# MCU.net
KiCad netlist of a schematic drawn in Altium Designer
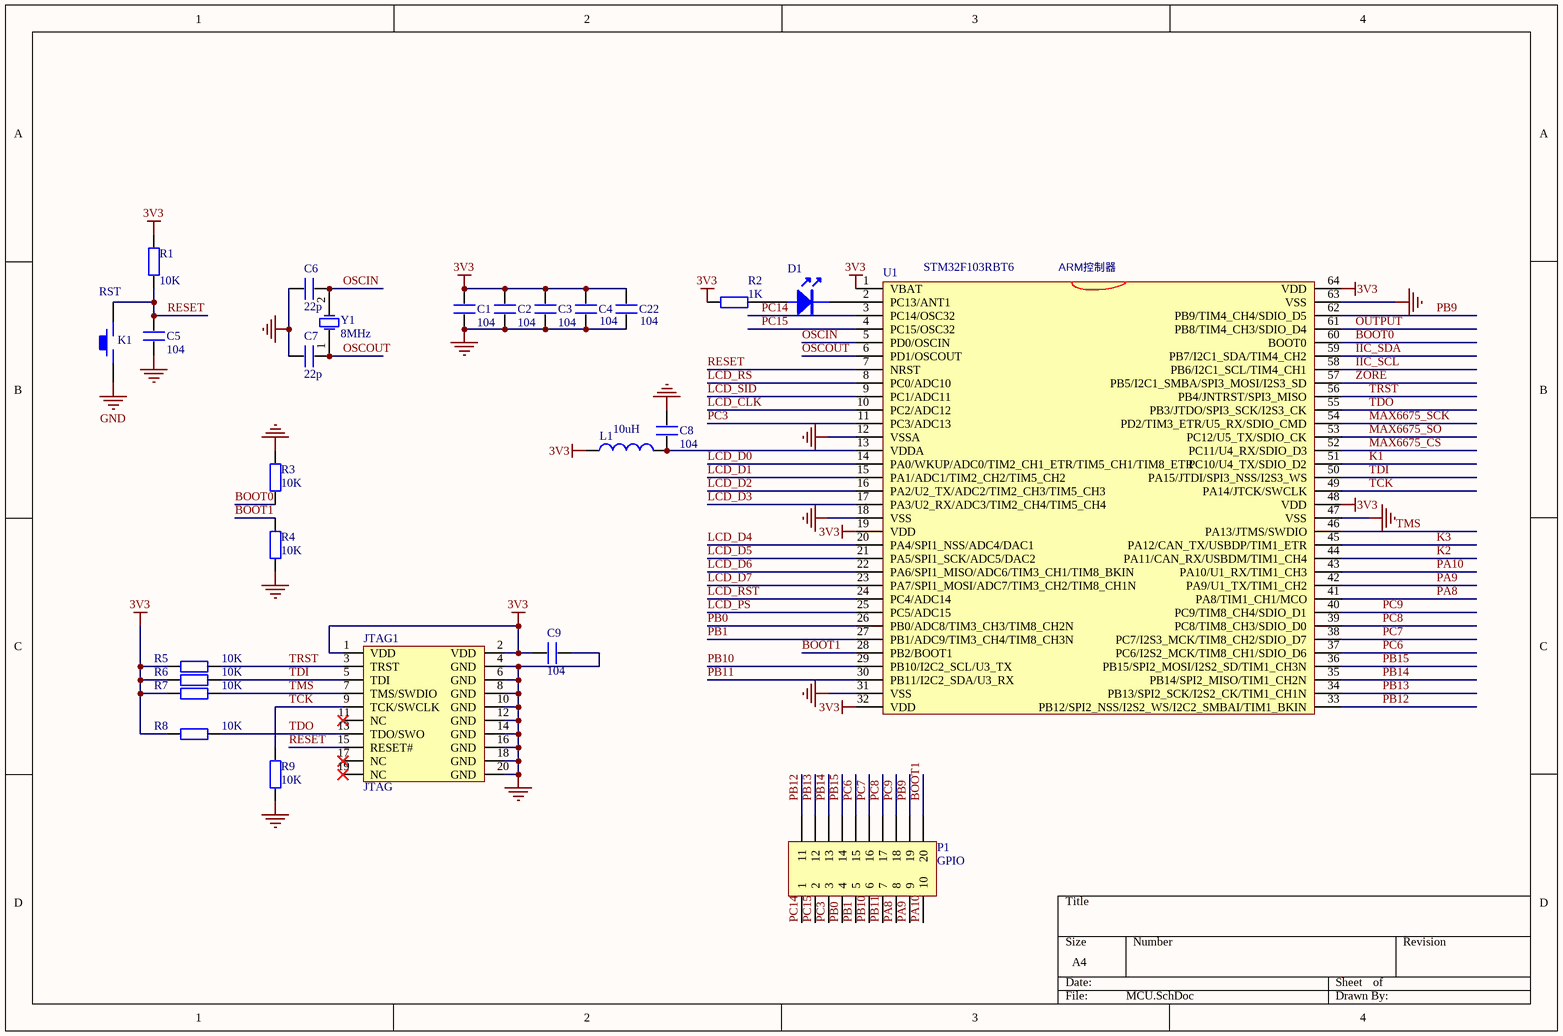
[diagram p0: MCU.SchDoc]

(export (version "E")
  (design (tool "Eeschema 10.0.6"))
  (components
    (comp (ref "C1") (value "104") (footprint "1206") (libsource (lib "MiniSTM32 V3.0封装库") (part "C")))
    (comp (ref "C2") (value "104") (footprint "1206") (libsource (lib "MiniSTM32 V3.0封装库") (part "C")))
    (comp (ref "C3") (value "104") (footprint "1206") (libsource (lib "MiniSTM32 V3.0封装库") (part "C")))
    (comp (ref "C4") (value "104") (footprint "1206") (libsource (lib "MiniSTM32 V3.0封装库") (part "C")))
    (comp (ref "C5") (value "104") (footprint "1206") (libsource (lib "MiniSTM32 V3.0封装库") (part "C")))
    (comp (ref "C6") (value "22p") (footprint "1206") (libsource (lib "MiniSTM32 V3.0封装库") (part "C")))
    (comp (ref "C7") (value "22p") (footprint "1206") (libsource (lib "MiniSTM32 V3.0封装库") (part "C")))
    (comp (ref "C8") (value "104") (footprint "1206") (libsource (lib "MiniSTM32 V3.0封装库") (part "C")))
    (comp (ref "C9") (value "104") (footprint "1206") (libsource (lib "MiniSTM32 V3.0封装库") (part "C")))
    (comp (ref "C22") (value "104") (footprint "1206") (libsource (lib "MiniSTM32 V3.0封装库") (part "C")))
    (comp (ref "D1") (value "~") (footprint "李建国1:LED") (libsource (lib "二极管") (part "发光二极管")))
    (comp (ref "JTAG1")
      (value "JTAG")
      (footprint "JTAG_20")
      (libsource (lib "MiniSTM32 V3.0封装库") (part "JTAG"))
    )
    (comp (ref "K1") (value "RST") (footprint "KEY_M") (libsource (lib "底板封装库") (part "KEY_M")))
    (comp (ref "L1")
      (value "10uH")
      (footprint "1206")
      (description "Inductor")
      (fields (field (name "PUBLISHER") "Altium Limited"))
      (libsource (lib "Miscellaneous Devices") (part "Inductor"))
    )
    (comp (ref "P1")
      (value "GPIO")
      (footprint "HDR2X10_CEN")
      (description "Header, 10-Pin, Dual row")
      (fields (field (name "PUBLISHER") "Altium Limited"))
      (libsource (lib "Miscellaneous Connectors") (part "Header 10X2A"))
    )
    (comp (ref "R1")
      (value "10K")
      (footprint "1206")
      (description "Resistor")
      (fields (field (name "PUBLISHER") "Altium Limited"))
      (libsource (lib "") (part "Res2_3"))
    )
    (comp (ref "R2")
      (value "1K")
      (footprint "1206")
      (description "Resistor")
      (fields (field (name "PUBLISHER") "Altium Limited"))
      (libsource (lib "") (part "Res2_1"))
    )
    (comp (ref "R3")
      (value "10K")
      (footprint "1206")
      (description "Resistor")
      (fields (field (name "PUBLISHER") "Altium Limited"))
      (libsource (lib "") (part "Res2_2"))
    )
    (comp (ref "R4")
      (value "10K")
      (footprint "1206")
      (description "Resistor")
      (fields (field (name "PUBLISHER") "Altium Limited"))
      (libsource (lib "") (part "Res2_2"))
    )
    (comp (ref "R5")
      (value "10K")
      (footprint "1206")
      (description "Resistor")
      (fields (field (name "PUBLISHER") "Altium Limited"))
      (libsource (lib "") (part "Res2_1"))
    )
    (comp (ref "R6")
      (value "10K")
      (footprint "1206")
      (description "Resistor")
      (fields (field (name "PUBLISHER") "Altium Limited"))
      (libsource (lib "Miscellaneous Devices") (part "Res2"))
    )
    (comp (ref "R7")
      (value "10K")
      (footprint "1206")
      (description "Resistor")
      (fields (field (name "PUBLISHER") "Altium Limited"))
      (libsource (lib "Miscellaneous Devices") (part "Res2"))
    )
    (comp (ref "R8")
      (value "10K")
      (footprint "1206")
      (description "Resistor")
      (fields (field (name "PUBLISHER") "Altium Limited"))
      (libsource (lib "Miscellaneous Devices") (part "Res2"))
    )
    (comp (ref "R9")
      (value "10K")
      (footprint "1206")
      (description "Resistor")
      (fields (field (name "PUBLISHER") "Altium Limited"))
      (libsource (lib "") (part "Res2_2"))
    )
    (comp (ref "U1")
      (value "STM32F103RBT6")
      (footprint "LQFP64")
      (libsource (lib "MiniSTM32 V3.0封装库") (part "STM32F103RDT6"))
    )
    (comp (ref "Y1")
      (value "8MHz")
      (footprint "XTAL_US")
      (description "Crystal Oscillator")
      (fields (field (name "PUBLISHER") "Altium Limited"))
      (libsource (lib "MiniSTM32 V3.0封装库") (part "XTAL"))
    )
  )
  (nets
    (net (code "1") (name "/BOOT0") (class "Default")
      (node (ref "R3") (pin "1") (pinfunction "1_1") (pintype "passive"))
      (node (ref "U1") (pin "60") (pinfunction "BOOT0_60") (pintype "passive"))
    )
    (net (code "2") (name "/BOOT1") (class "Default")
      (node (ref "P1") (pin "20") (pinfunction "20_20") (pintype "passive"))
      (node (ref "R4") (pin "2") (pinfunction "2_2") (pintype "passive"))
      (node (ref "U1") (pin "28") (pinfunction "PB2/BOOT1_28") (pintype "passive"))
    )
    (net (code "3") (name "/IIC_SCL") (class "Default")
      (node (ref "U1") (pin "58") (pinfunction "PB6/I2C1_SCL/TIM4_CH1_58") (pintype "passive"))
    )
    (net (code "4") (name "/IIC_SDA") (class "Default")
      (node (ref "U1") (pin "59") (pinfunction "PB7/I2C1_SDA/TIM4_CH2_59") (pintype "passive"))
    )
    (net (code "5") (name "/K1") (class "Default")
      (node (ref "U1") (pin "51") (pinfunction "PC10/U4_TX/SDIO_D2_51") (pintype "passive"))
    )
    (net (code "6") (name "/K2") (class "Default")
      (node (ref "U1") (pin "44") (pinfunction "PA11/CAN_RX/USBDM/TIM1_CH4_44") (pintype "passive"))
    )
    (net (code "7") (name "/K3") (class "Default")
      (node (ref "U1") (pin "45") (pinfunction "PA12/CAN_TX/USBDP/TIM1_ETR_45") (pintype "passive"))
    )
    (net (code "8") (name "/LCD_CLK") (class "Default")
      (node (ref "U1") (pin "10") (pinfunction "PC2/ADC12_10") (pintype "passive"))
    )
    (net (code "9") (name "/LCD_D0") (class "Default")
      (node (ref "U1") (pin "14") (pinfunction "PA0/WKUP/ADC0/TIM2_CH1_ETR/TIM5_CH1/TIM8_ETR_14") (pintype "passive"))
    )
    (net (code "10") (name "/LCD_D1") (class "Default")
      (node (ref "U1") (pin "15") (pinfunction "PA1/ADC1/TIM2_CH2/TIM5_CH2_15") (pintype "passive"))
    )
    (net (code "11") (name "/LCD_D2") (class "Default")
      (node (ref "U1") (pin "16") (pinfunction "PA2/U2_TX/ADC2/TIM2_CH3/TIM5_CH3_16") (pintype "passive"))
    )
    (net (code "12") (name "/LCD_D3") (class "Default")
      (node (ref "U1") (pin "17") (pinfunction "PA3/U2_RX/ADC3/TIM2_CH4/TIM5_CH4_17") (pintype "passive"))
    )
    (net (code "13") (name "/LCD_D4") (class "Default")
      (node (ref "U1") (pin "20") (pinfunction "PA4/SPI1_NSS/ADC4/DAC1_20") (pintype "passive"))
    )
    (net (code "14") (name "/LCD_D5") (class "Default")
      (node (ref "U1") (pin "21") (pinfunction "PA5/SPI1_SCK/ADC5/DAC2_21") (pintype "passive"))
    )
    (net (code "15") (name "/LCD_D6") (class "Default")
      (node (ref "U1") (pin "22") (pinfunction "PA6/SPI1_MISO/ADC6/TIM3_CH1/TIM8_BKIN_22") (pintype "passive"))
    )
    (net (code "16") (name "/LCD_D7") (class "Default")
      (node (ref "U1") (pin "23") (pinfunction "PA7/SPI1_MOSI/ADC7/TIM3_CH2/TIM8_CH1N_23") (pintype "passive"))
    )
    (net (code "17") (name "/LCD_PS") (class "Default")
      (node (ref "U1") (pin "25") (pinfunction "PC5/ADC15_25") (pintype "passive"))
    )
    (net (code "18") (name "/LCD_RS") (class "Default")
      (node (ref "U1") (pin "8") (pinfunction "PC0/ADC10_8") (pintype "passive"))
    )
    (net (code "19") (name "/LCD_RST") (class "Default")
      (node (ref "U1") (pin "24") (pinfunction "PC4/ADC14_24") (pintype "passive"))
    )
    (net (code "20") (name "/LCD_SID") (class "Default")
      (node (ref "U1") (pin "9") (pinfunction "PC1/ADC11_9") (pintype "passive"))
    )
    (net (code "21") (name "/MAX6675_CS") (class "Default")
      (node (ref "U1") (pin "52") (pinfunction "PC11/U4_RX/SDIO_D3_52") (pintype "passive"))
    )
    (net (code "22") (name "/MAX6675_SCK") (class "Default")
      (node (ref "U1") (pin "54") (pinfunction "PD2/TIM3_ETR/U5_RX/SDIO_CMD_54") (pintype "passive"))
    )
    (net (code "23") (name "/MAX6675_SO") (class "Default")
      (node (ref "U1") (pin "53") (pinfunction "PC12/U5_TX/SDIO_CK_53") (pintype "passive"))
    )
    (net (code "24") (name "/OSCIN") (class "Default")
      (node (ref "C6") (pin "1") (pintype "passive"))
      (node (ref "U1") (pin "5") (pinfunction "PD0/OSCIN_5") (pintype "passive"))
      (node (ref "Y1") (pin "2") (pinfunction "OSC2_2") (pintype "passive"))
    )
    (net (code "25") (name "/OSCOUT") (class "Default")
      (node (ref "C7") (pin "2") (pintype "passive"))
      (node (ref "U1") (pin "6") (pinfunction "PD1/OSCOUT_6") (pintype "passive"))
      (node (ref "Y1") (pin "1") (pinfunction "OSC1_1") (pintype "passive"))
    )
    (net (code "26") (name "/OUTPUT") (class "Default")
      (node (ref "U1") (pin "61") (pinfunction "PB8/TIM4_CH3/SDIO_D4_61") (pintype "passive"))
    )
    (net (code "27") (name "/PA8") (class "Default")
      (node (ref "P1") (pin "8") (pinfunction "8_8") (pintype "passive"))
      (node (ref "U1") (pin "41") (pinfunction "PA8/TIM1_CH1/MCO_41") (pintype "passive"))
    )
    (net (code "28") (name "/PA9") (class "Default")
      (node (ref "P1") (pin "9") (pinfunction "9_9") (pintype "passive"))
      (node (ref "U1") (pin "42") (pinfunction "PA9/U1_TX/TIM1_CH2_42") (pintype "passive"))
    )
    (net (code "29") (name "/PA10") (class "Default")
      (node (ref "P1") (pin "10") (pinfunction "10_10") (pintype "passive"))
      (node (ref "U1") (pin "43") (pinfunction "PA10/U1_RX/TIM1_CH3_43") (pintype "passive"))
    )
    (net (code "30") (name "/PB0") (class "Default")
      (node (ref "P1") (pin "4") (pinfunction "4_4") (pintype "passive"))
      (node (ref "U1") (pin "26") (pinfunction "PB0/ADC8/TIM3_CH3/TIM8_CH2N_26") (pintype "passive"))
    )
    (net (code "31") (name "/PB1") (class "Default")
      (node (ref "P1") (pin "5") (pinfunction "5_5") (pintype "passive"))
      (node (ref "U1") (pin "27") (pinfunction "PB1/ADC9/TIM3_CH4/TIM8_CH3N_27") (pintype "passive"))
    )
    (net (code "32") (name "/PB9") (class "Default")
      (node (ref "P1") (pin "19") (pinfunction "19_19") (pintype "passive"))
      (node (ref "U1") (pin "62") (pinfunction "PB9/TIM4_CH4/SDIO_D5_62") (pintype "passive"))
    )
    (net (code "33") (name "/PB10") (class "Default")
      (node (ref "P1") (pin "6") (pinfunction "6_6") (pintype "passive"))
      (node (ref "U1") (pin "29") (pinfunction "PB10/I2C2_SCL/U3_TX_29") (pintype "passive"))
    )
    (net (code "34") (name "/PB11") (class "Default")
      (node (ref "P1") (pin "7") (pinfunction "7_7") (pintype "passive"))
      (node (ref "U1") (pin "30") (pinfunction "PB11/I2C2_SDA/U3_RX_30") (pintype "passive"))
    )
    (net (code "35") (name "/PB12") (class "Default")
      (node (ref "P1") (pin "11") (pinfunction "11_11") (pintype "passive"))
      (node (ref "U1") (pin "33") (pinfunction "PB12/SPI2_NSS/I2S2_WS/I2C2_SMBAI/TIM1_BKIN_33") (pintype "passive"))
    )
    (net (code "36") (name "/PB13") (class "Default")
      (node (ref "P1") (pin "12") (pinfunction "12_12") (pintype "passive"))
      (node (ref "U1") (pin "34") (pinfunction "PB13/SPI2_SCK/I2S2_CK/TIM1_CH1N_34") (pintype "passive"))
    )
    (net (code "37") (name "/PB14") (class "Default")
      (node (ref "P1") (pin "13") (pinfunction "13_13") (pintype "passive"))
      (node (ref "U1") (pin "35") (pinfunction "PB14/SPI2_MISO/TIM1_CH2N_35") (pintype "passive"))
    )
    (net (code "38") (name "/PB15") (class "Default")
      (node (ref "P1") (pin "14") (pinfunction "14_14") (pintype "passive"))
      (node (ref "U1") (pin "36") (pinfunction "PB15/SPI2_MOSI/I2S2_SD/TIM1_CH3N_36") (pintype "passive"))
    )
    (net (code "39") (name "/PC3") (class "Default")
      (node (ref "P1") (pin "3") (pinfunction "3_3") (pintype "passive"))
      (node (ref "U1") (pin "11") (pinfunction "PC3/ADC13_11") (pintype "passive"))
    )
    (net (code "40") (name "/PC6") (class "Default")
      (node (ref "P1") (pin "15") (pinfunction "15_15") (pintype "passive"))
      (node (ref "U1") (pin "37") (pinfunction "PC6/I2S2_MCK/TIM8_CH1/SDIO_D6_37") (pintype "passive"))
    )
    (net (code "41") (name "/PC7") (class "Default")
      (node (ref "P1") (pin "16") (pinfunction "16_16") (pintype "passive"))
      (node (ref "U1") (pin "38") (pinfunction "PC7/I2S3_MCK/TIM8_CH2/SDIO_D7_38") (pintype "passive"))
    )
    (net (code "42") (name "/PC8") (class "Default")
      (node (ref "P1") (pin "17") (pinfunction "17_17") (pintype "passive"))
      (node (ref "U1") (pin "39") (pinfunction "PC8/TIM8_CH3/SDIO_D0_39") (pintype "passive"))
    )
    (net (code "43") (name "/PC9") (class "Default")
      (node (ref "P1") (pin "18") (pinfunction "18_18") (pintype "passive"))
      (node (ref "U1") (pin "40") (pinfunction "PC9/TIM8_CH4/SDIO_D1_40") (pintype "passive"))
    )
    (net (code "44") (name "/PC14") (class "Default")
      (node (ref "P1") (pin "1") (pinfunction "1_1") (pintype "passive"))
      (node (ref "U1") (pin "3") (pinfunction "PC14/OSC32_3") (pintype "passive"))
    )
    (net (code "45") (name "/PC15") (class "Default")
      (node (ref "P1") (pin "2") (pinfunction "2_2") (pintype "passive"))
      (node (ref "U1") (pin "4") (pinfunction "PC15/OSC32_4") (pintype "passive"))
    )
    (net (code "46") (name "/RESET") (class "Default")
      (node (ref "C5") (pin "1") (pintype "passive"))
      (node (ref "JTAG1") (pin "15") (pinfunction "RESET#_15") (pintype "passive"))
      (node (ref "K1") (pin "2") (pinfunction "2_2") (pintype "passive"))
      (node (ref "R1") (pin "2") (pinfunction "2_2") (pintype "passive"))
      (node (ref "U1") (pin "7") (pinfunction "NRST_7") (pintype "passive"))
    )
    (net (code "47") (name "/TCK") (class "Default")
      (node (ref "JTAG1") (pin "9") (pinfunction "TCK/SWCLK_9") (pintype "passive"))
      (node (ref "R9") (pin "2") (pinfunction "2_2") (pintype "passive"))
      (node (ref "U1") (pin "49") (pinfunction "PA14/JTCK/SWCLK_49") (pintype "passive"))
    )
    (net (code "48") (name "/TDI") (class "Default")
      (node (ref "JTAG1") (pin "5") (pinfunction "TDI_5") (pintype "passive"))
      (node (ref "R6") (pin "1") (pinfunction "1_1") (pintype "passive"))
      (node (ref "U1") (pin "50") (pinfunction "PA15/JTDI/SPI3_NSS/I2S3_WS_50") (pintype "passive"))
    )
    (net (code "49") (name "/TDO") (class "Default")
      (node (ref "JTAG1") (pin "13") (pinfunction "TDO/SWO_13") (pintype "passive"))
      (node (ref "R8") (pin "1") (pinfunction "1_1") (pintype "passive"))
      (node (ref "U1") (pin "55") (pinfunction "PB3/JTDO/SPI3_SCK/I2S3_CK_55") (pintype "passive"))
    )
    (net (code "50") (name "/TMS") (class "Default")
      (node (ref "JTAG1") (pin "7") (pinfunction "TMS/SWDIO_7") (pintype "passive"))
      (node (ref "R7") (pin "1") (pinfunction "1_1") (pintype "passive"))
      (node (ref "U1") (pin "46") (pinfunction "PA13/JTMS/SWDIO_46") (pintype "passive"))
    )
    (net (code "51") (name "/TRST") (class "Default")
      (node (ref "JTAG1") (pin "3") (pinfunction "TRST_3") (pintype "passive"))
      (node (ref "R5") (pin "2") (pinfunction "2_2") (pintype "passive"))
      (node (ref "U1") (pin "56") (pinfunction "PB4/JNTRST/SPI3_MISO_56") (pintype "passive"))
    )
    (net (code "52") (name "/ZORE") (class "Default")
      (node (ref "U1") (pin "57") (pinfunction "PB5/I2C1_SMBA/SPI3_MOSI/I2S3_SD_57") (pintype "passive"))
    )
    (net (code "53") (name "3V3") (class "Default")
      (node (ref "C1") (pin "1") (pintype "passive"))
      (node (ref "C2") (pin "1") (pintype "passive"))
      (node (ref "C22") (pin "1") (pintype "passive"))
      (node (ref "C3") (pin "1") (pintype "passive"))
      (node (ref "C4") (pin "1") (pintype "passive"))
      (node (ref "C9") (pin "1") (pintype "passive"))
      (node (ref "JTAG1") (pin "1") (pinfunction "VDD_1") (pintype "passive"))
      (node (ref "JTAG1") (pin "2") (pinfunction "VDD_2") (pintype "passive"))
      (node (ref "L1") (pin "1") (pinfunction "1_1") (pintype "passive"))
      (node (ref "R1") (pin "1") (pinfunction "1_1") (pintype "passive"))
      (node (ref "R2") (pin "1") (pinfunction "1_1") (pintype "passive"))
      (node (ref "R5") (pin "1") (pinfunction "1_1") (pintype "passive"))
      (node (ref "R6") (pin "2") (pinfunction "2_2") (pintype "passive"))
      (node (ref "R7") (pin "2") (pinfunction "2_2") (pintype "passive"))
      (node (ref "R8") (pin "2") (pinfunction "2_2") (pintype "passive"))
      (node (ref "U1") (pin "1") (pinfunction "VBAT_1") (pintype "passive"))
      (node (ref "U1") (pin "19") (pinfunction "VDD_19") (pintype "passive"))
      (node (ref "U1") (pin "32") (pinfunction "VDD_32") (pintype "passive"))
      (node (ref "U1") (pin "48") (pinfunction "VDD_48") (pintype "passive"))
      (node (ref "U1") (pin "64") (pinfunction "VDD_64") (pintype "passive"))
    )
    (net (code "54") (name "GND") (class "Default")
      (node (ref "C1") (pin "2") (pintype "passive"))
      (node (ref "C2") (pin "2") (pintype "passive"))
      (node (ref "C22") (pin "2") (pintype "passive"))
      (node (ref "C3") (pin "2") (pintype "passive"))
      (node (ref "C4") (pin "2") (pintype "passive"))
      (node (ref "C5") (pin "2") (pintype "passive"))
      (node (ref "C6") (pin "2") (pintype "passive"))
      (node (ref "C7") (pin "1") (pintype "passive"))
      (node (ref "C8") (pin "1") (pintype "passive"))
      (node (ref "C9") (pin "2") (pintype "passive"))
      (node (ref "JTAG1") (pin "10") (pinfunction "GND_10") (pintype "passive"))
      (node (ref "JTAG1") (pin "12") (pinfunction "GND_12") (pintype "passive"))
      (node (ref "JTAG1") (pin "14") (pinfunction "GND_14") (pintype "passive"))
      (node (ref "JTAG1") (pin "16") (pinfunction "GND_16") (pintype "passive"))
      (node (ref "JTAG1") (pin "18") (pinfunction "GND_18") (pintype "passive"))
      (node (ref "JTAG1") (pin "20") (pinfunction "GND_20") (pintype "passive"))
      (node (ref "JTAG1") (pin "4") (pinfunction "GND_4") (pintype "passive"))
      (node (ref "JTAG1") (pin "6") (pinfunction "GND_6") (pintype "passive"))
      (node (ref "JTAG1") (pin "8") (pinfunction "GND_8") (pintype "passive"))
      (node (ref "K1") (pin "1") (pinfunction "1_1") (pintype "passive"))
      (node (ref "R3") (pin "2") (pinfunction "2_2") (pintype "passive"))
      (node (ref "R4") (pin "1") (pinfunction "1_1") (pintype "passive"))
      (node (ref "R9") (pin "1") (pinfunction "1_1") (pintype "passive"))
      (node (ref "U1") (pin "12") (pinfunction "VSSA_12") (pintype "passive"))
      (node (ref "U1") (pin "18") (pinfunction "VSS_18") (pintype "passive"))
      (node (ref "U1") (pin "31") (pinfunction "VSS_31") (pintype "passive"))
      (node (ref "U1") (pin "47") (pinfunction "VSS_47") (pintype "passive"))
      (node (ref "U1") (pin "63") (pinfunction "VSS_63") (pintype "passive"))
    )
    (net (code "55") (name "Net-(D1-1)") (class "Default")
      (node (ref "D1") (pin "A") (pinfunction "1_A") (pintype "passive"))
      (node (ref "R2") (pin "2") (pinfunction "2_2") (pintype "passive"))
    )
    (net (code "56") (name "Net-(D1-2)") (class "Default")
      (node (ref "D1") (pin "K") (pinfunction "2_K") (pintype "passive"))
      (node (ref "U1") (pin "2") (pinfunction "PC13/ANT1_2") (pintype "passive"))
    )
    (net (code "57") (name "Net-(U1-VDDA)") (class "Default")
      (node (ref "C8") (pin "2") (pintype "passive"))
      (node (ref "L1") (pin "2") (pinfunction "2_2") (pintype "passive"))
      (node (ref "U1") (pin "13") (pinfunction "VDDA_13") (pintype "passive"))
    )
    (net (code "58") (name "unconnected-(JTAG1-NC-Pad11)") (class "Default")
      (node (ref "JTAG1") (pin "11") (pinfunction "NC_11") (pintype "passive+no_connect"))
    )
    (net (code "59") (name "unconnected-(JTAG1-NC-Pad17)") (class "Default")
      (node (ref "JTAG1") (pin "17") (pinfunction "NC_17") (pintype "passive+no_connect"))
    )
    (net (code "60") (name "unconnected-(JTAG1-NC-Pad19)") (class "Default")
      (node (ref "JTAG1") (pin "19") (pinfunction "NC_19") (pintype "passive+no_connect"))
    )
  )
)
